# sd_logger.net
KiCad netlist of a schematic drawn in EAGLE
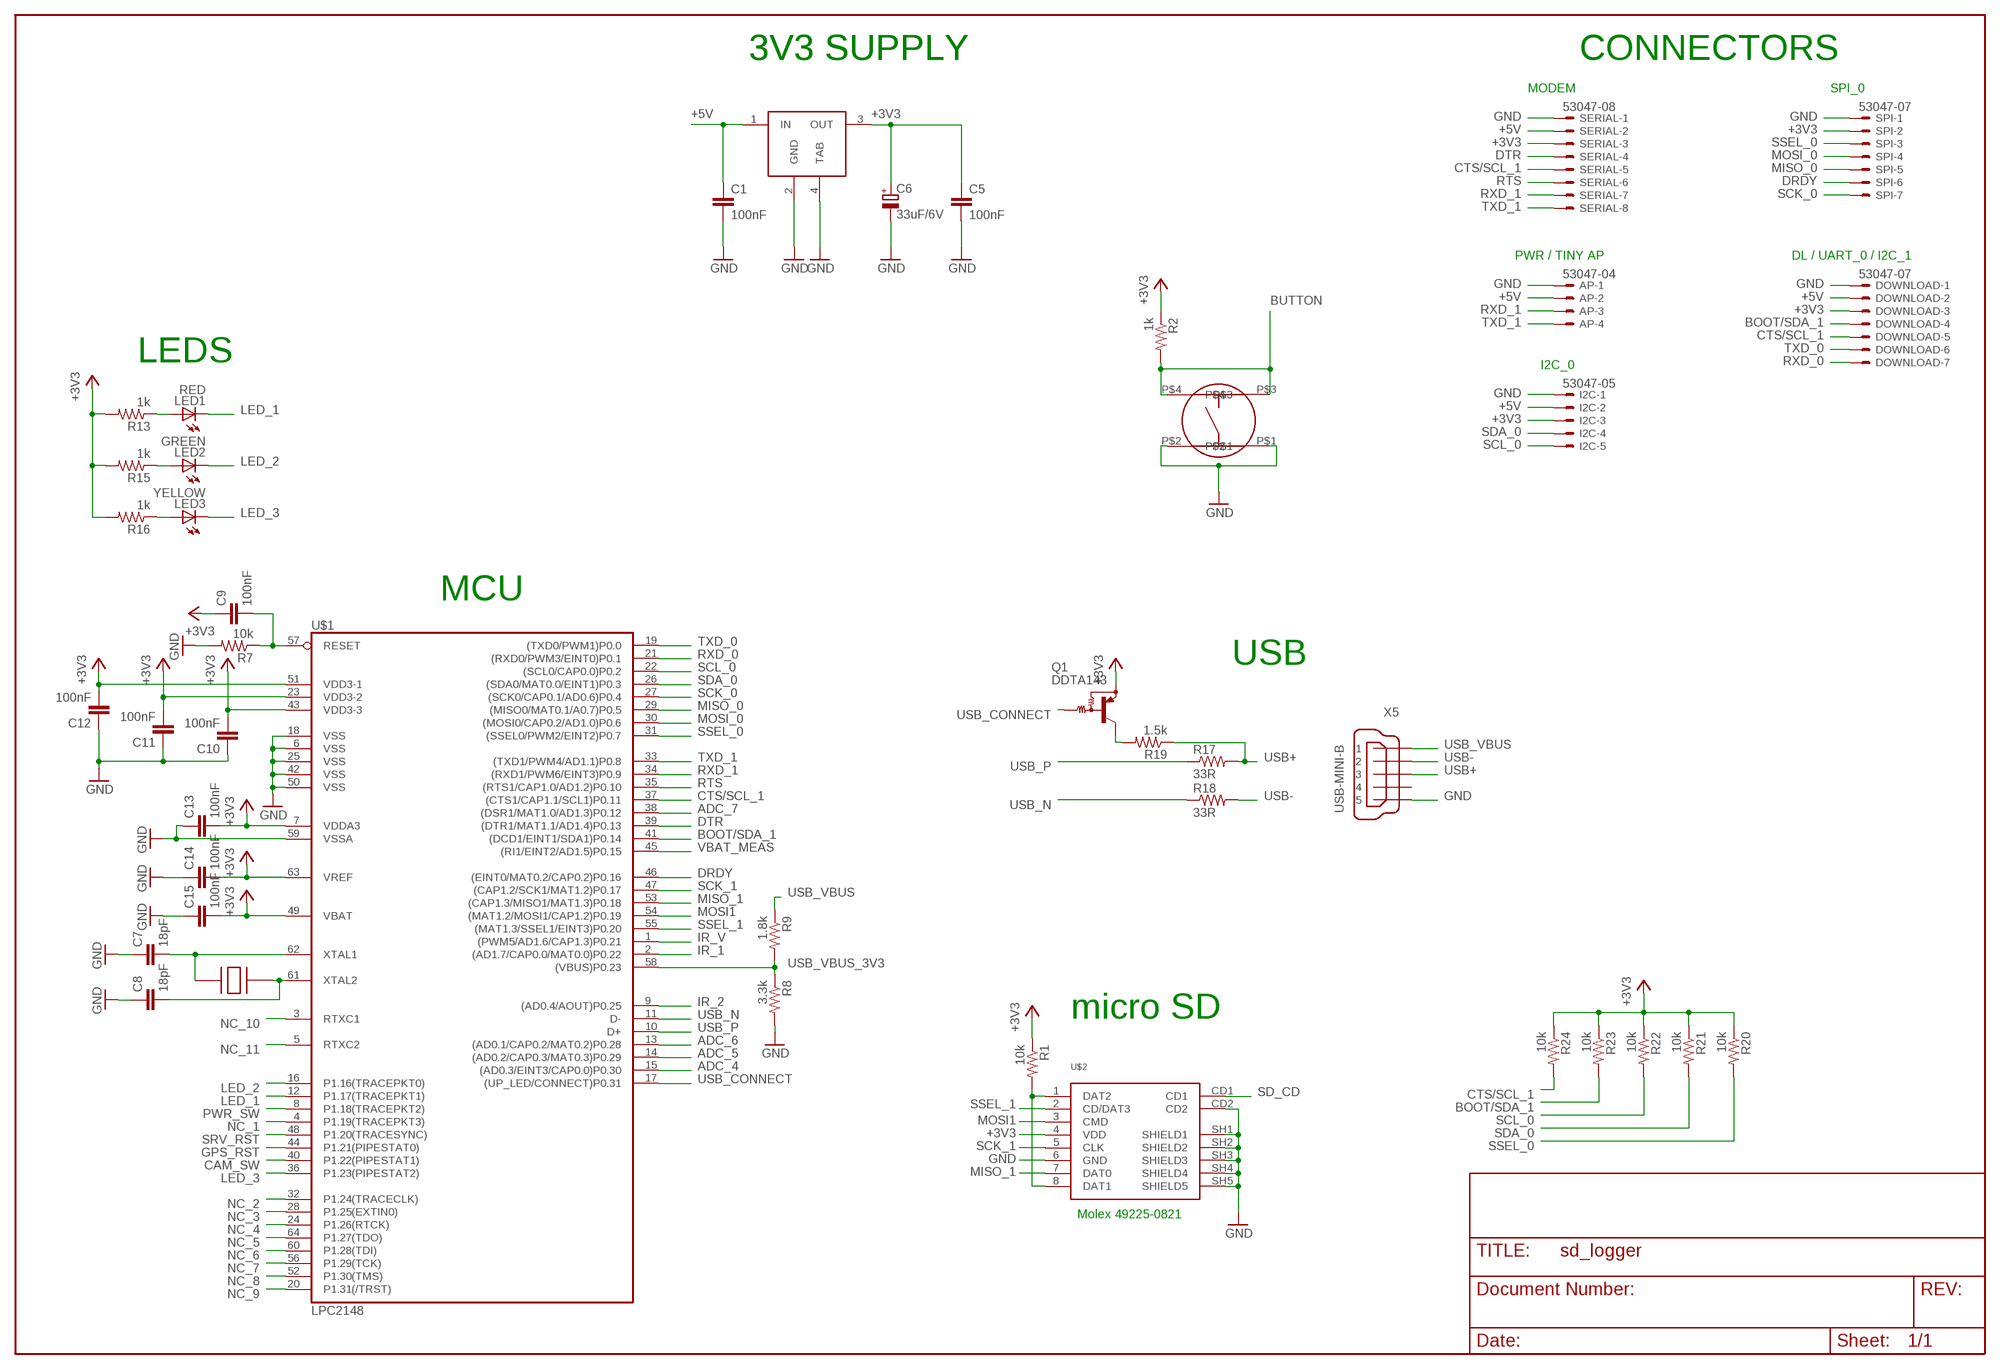
[diagram p0: schematic, sheet 1]

(export (version "E")
  (design (tool "Eeschema 10.0.6"))
  (components
    (comp (ref "AP")
      (value "53047-04")
      (footprint "eagle-import:53047-04")
      (libsource (lib "eagle-import") (part "53?-04047"))
    )
    (comp (ref "C1")
      (value "100nF")
      (footprint "eagle-import:C0603")
      (libsource (lib "eagle-import") (part "C-EUC0603"))
    )
    (comp (ref "C5")
      (value "100nF")
      (footprint "eagle-import:C0603")
      (libsource (lib "eagle-import") (part "C-EUC0603"))
    )
    (comp (ref "C6")
      (value "33uF/6V")
      (footprint "eagle-import:CT3216")
      (libsource (lib "eagle-import") (part "CPOL-EUCT3216"))
    )
    (comp (ref "C7")
      (value "18pF")
      (footprint "eagle-import:C0603")
      (libsource (lib "eagle-import") (part "C-EUC0603"))
    )
    (comp (ref "C8")
      (value "18pF")
      (footprint "eagle-import:C0603")
      (libsource (lib "eagle-import") (part "C-EUC0603"))
    )
    (comp (ref "C9")
      (value "100nF")
      (footprint "eagle-import:C0603")
      (libsource (lib "eagle-import") (part "C-EUC0603"))
    )
    (comp (ref "C10")
      (value "100nF")
      (footprint "eagle-import:C0603")
      (libsource (lib "eagle-import") (part "C-EUC0603"))
    )
    (comp (ref "C11")
      (value "100nF")
      (footprint "eagle-import:C0603")
      (libsource (lib "eagle-import") (part "C-EUC0603"))
    )
    (comp (ref "C12")
      (value "100nF")
      (footprint "eagle-import:C0603")
      (libsource (lib "eagle-import") (part "C-EUC0603"))
    )
    (comp (ref "C13")
      (value "100nF")
      (footprint "eagle-import:C0603")
      (libsource (lib "eagle-import") (part "C-EUC0603"))
    )
    (comp (ref "C14")
      (value "100nF")
      (footprint "eagle-import:C0603")
      (libsource (lib "eagle-import") (part "C-EUC0603"))
    )
    (comp (ref "C15")
      (value "100nF")
      (footprint "eagle-import:C0603")
      (libsource (lib "eagle-import") (part "C-EUC0603"))
    )
    (comp (ref "DOWNLOAD")
      (value "53047-07")
      (footprint "eagle-import:53047-07")
      (libsource (lib "eagle-import") (part "53?-07047"))
    )
    (comp (ref "I2C")
      (value "53047-05")
      (footprint "eagle-import:53047-05")
      (libsource (lib "eagle-import") (part "53?-05047"))
    )
    (comp (ref "LED1")
      (value "RED")
      (footprint "eagle-import:CHIP-LED0805")
      (libsource (lib "eagle-import") (part "LEDCHIP-LED0805"))
    )
    (comp (ref "LED2")
      (value "GREEN")
      (footprint "eagle-import:CHIP-LED0805")
      (libsource (lib "eagle-import") (part "LEDCHIP-LED0805"))
    )
    (comp (ref "LED3")
      (value "YELLOW")
      (footprint "eagle-import:CHIP-LED0805")
      (libsource (lib "eagle-import") (part "LEDCHIP-LED0805"))
    )
    (comp (ref "Q1")
      (value "DDTA143")
      (footprint "eagle-import:SC59-BEC")
      (libsource (lib "eagle-import") (part "MUN2111T1"))
    )
    (comp (ref "R1")
      (value "10k")
      (footprint "eagle-import:R0603@1")
      (libsource (lib "eagle-import") (part "R-US_R0603"))
    )
    (comp (ref "R2")
      (value "1k")
      (footprint "eagle-import:R0603@1")
      (libsource (lib "eagle-import") (part "R-US_R0603"))
    )
    (comp (ref "R7")
      (value "10k")
      (footprint "eagle-import:R0603@1")
      (libsource (lib "eagle-import") (part "R-US_R0603"))
    )
    (comp (ref "R8")
      (value "3.3k")
      (footprint "eagle-import:R0603@1")
      (libsource (lib "eagle-import") (part "R-US_R0603"))
    )
    (comp (ref "R9")
      (value "1.8k")
      (footprint "eagle-import:R0603@1")
      (libsource (lib "eagle-import") (part "R-US_R0603"))
    )
    (comp (ref "R13")
      (value "1k")
      (footprint "eagle-import:R0603@1")
      (libsource (lib "eagle-import") (part "R-US_R0603"))
    )
    (comp (ref "R15")
      (value "1k")
      (footprint "eagle-import:R0603@1")
      (libsource (lib "eagle-import") (part "R-US_R0603"))
    )
    (comp (ref "R16")
      (value "1k")
      (footprint "eagle-import:R0603@1")
      (libsource (lib "eagle-import") (part "R-US_R0603"))
    )
    (comp (ref "R17")
      (value "33R")
      (footprint "eagle-import:R0603@1")
      (libsource (lib "eagle-import") (part "R-US_R0603"))
    )
    (comp (ref "R18")
      (value "33R")
      (footprint "eagle-import:R0603@1")
      (libsource (lib "eagle-import") (part "R-US_R0603"))
    )
    (comp (ref "R19")
      (value "1.5k")
      (footprint "eagle-import:R0603@1")
      (libsource (lib "eagle-import") (part "R-US_R0603"))
    )
    (comp (ref "R20")
      (value "10k")
      (footprint "eagle-import:R0603@1")
      (libsource (lib "eagle-import") (part "R-US_R0603"))
    )
    (comp (ref "R21")
      (value "10k")
      (footprint "eagle-import:R0603@1")
      (libsource (lib "eagle-import") (part "R-US_R0603"))
    )
    (comp (ref "R22")
      (value "10k")
      (footprint "eagle-import:R0603@1")
      (libsource (lib "eagle-import") (part "R-US_R0603"))
    )
    (comp (ref "R23")
      (value "10k")
      (footprint "eagle-import:R0603@1")
      (libsource (lib "eagle-import") (part "R-US_R0603"))
    )
    (comp (ref "R24")
      (value "10k")
      (footprint "eagle-import:R0603@1")
      (libsource (lib "eagle-import") (part "R-US_R0603"))
    )
    (comp (ref "SERIAL")
      (value "53047-08")
      (footprint "eagle-import:53047-08")
      (libsource (lib "eagle-import") (part "53?-08047"))
    )
    (comp (ref "SPI")
      (value "53047-07")
      (footprint "eagle-import:53047-07")
      (libsource (lib "eagle-import") (part "53?-07047"))
    )
    (comp (ref "SW1")
      (value "B3S")
      (footprint "eagle-import:B3S")
      (libsource (lib "eagle-import") (part "B3S"))
    )
    (comp (ref "U$1")
      (value "LPC2148")
      (footprint "eagle-import:SQFP-S-10X10-64")
      (libsource (lib "eagle-import") (part "LPC2148"))
    )
    (comp (ref "U$2")
      (value "MICRO_SD")
      (footprint "eagle-import:SD-MOLEX-49225")
      (libsource (lib "eagle-import") (part "MICRO_SD"))
    )
    (comp (ref "U$3")
      (value "LM3940IMP-3.3")
      (footprint "eagle-import:SOT223-R")
      (libsource (lib "eagle-import") (part "LM3940IMP-3.3"))
    )
    (comp (ref "U$4")
      (value "CRYSTAL_CTS")
      (footprint "eagle-import:CTS_CRYSTAL")
      (libsource (lib "eagle-import") (part "CRYSTAL_CTS"))
    )
    (comp (ref "X5")
      (value "USB-MINI-B")
      (footprint "eagle-import:UX60-MB-5ST")
      (libsource (lib "eagle-import") (part "MINI-USB-UX60-MB-5ST"))
    )
  )
  (nets
    (net (code "1") (name "+3V3") (class "Default")
      (node (ref "C10") (pin "2") (pinfunction "2_2") (pintype "passive"))
      (node (ref "C11") (pin "2") (pinfunction "2_2") (pintype "passive"))
      (node (ref "C12") (pin "2") (pinfunction "2_2") (pintype "passive"))
      (node (ref "C13") (pin "2") (pinfunction "2_2") (pintype "passive"))
      (node (ref "C14") (pin "2") (pinfunction "2_2") (pintype "passive"))
      (node (ref "C15") (pin "2") (pinfunction "2_2") (pintype "passive"))
      (node (ref "C5") (pin "1") (pinfunction "1_1") (pintype "passive"))
      (node (ref "C6") (pin "+") (pinfunction "+_+") (pintype "passive"))
      (node (ref "C9") (pin "1") (pinfunction "1_1") (pintype "passive"))
      (node (ref "DOWNLOAD") (pin "3") (pinfunction "S_3") (pintype "passive"))
      (node (ref "I2C") (pin "3") (pinfunction "S_3") (pintype "passive"))
      (node (ref "Q1") (pin "E") (pinfunction "E_E") (pintype "passive"))
      (node (ref "R1") (pin "1") (pinfunction "1_1") (pintype "passive"))
      (node (ref "R13") (pin "2") (pinfunction "2_2") (pintype "passive"))
      (node (ref "R15") (pin "2") (pinfunction "2_2") (pintype "passive"))
      (node (ref "R16") (pin "2") (pinfunction "2_2") (pintype "passive"))
      (node (ref "R2") (pin "1") (pinfunction "1_1") (pintype "passive"))
      (node (ref "R20") (pin "1") (pinfunction "1_1") (pintype "passive"))
      (node (ref "R21") (pin "1") (pinfunction "1_1") (pintype "passive"))
      (node (ref "R22") (pin "1") (pinfunction "1_1") (pintype "passive"))
      (node (ref "R23") (pin "1") (pinfunction "1_1") (pintype "passive"))
      (node (ref "R24") (pin "1") (pinfunction "1_1") (pintype "passive"))
      (node (ref "SERIAL") (pin "3") (pinfunction "S_3") (pintype "passive"))
      (node (ref "SPI") (pin "2") (pinfunction "S_2") (pintype "passive"))
      (node (ref "U$1") (pin "23") (pinfunction "VDD3-2_23") (pintype "power_in"))
      (node (ref "U$1") (pin "43") (pinfunction "VDD3-3_43") (pintype "power_in"))
      (node (ref "U$1") (pin "49") (pinfunction "VBAT_49") (pintype "power_in"))
      (node (ref "U$1") (pin "51") (pinfunction "VDD3-1_51") (pintype "power_in"))
      (node (ref "U$1") (pin "63") (pinfunction "VREF_63") (pintype "input"))
      (node (ref "U$1") (pin "7") (pinfunction "VDDA3_7") (pintype "power_in"))
      (node (ref "U$2") (pin "4") (pinfunction "VDD_4") (pintype "power_in"))
      (node (ref "U$3") (pin "3") (pinfunction "OUT_3") (pintype "bidirectional"))
    )
    (net (code "2") (name "/+5V") (class "Default")
      (node (ref "AP") (pin "2") (pinfunction "S_2") (pintype "passive"))
      (node (ref "C1") (pin "1") (pinfunction "1_1") (pintype "passive"))
      (node (ref "DOWNLOAD") (pin "2") (pinfunction "S_2") (pintype "passive"))
      (node (ref "I2C") (pin "2") (pinfunction "S_2") (pintype "passive"))
      (node (ref "SERIAL") (pin "2") (pinfunction "S_2") (pintype "passive"))
      (node (ref "U$3") (pin "1") (pinfunction "IN_1") (pintype "bidirectional"))
    )
    (net (code "3") (name "/ADC_4") (class "Default")
      (node (ref "U$1") (pin "15") (pinfunction "(AD0.3/EINT3/CAP0.0)P0.30_15") (pintype "bidirectional"))
    )
    (net (code "4") (name "/ADC_5") (class "Default")
      (node (ref "U$1") (pin "14") (pinfunction "(AD0.2/CAP0.3/MAT0.3)P0.29_14") (pintype "bidirectional"))
    )
    (net (code "5") (name "/ADC_6") (class "Default")
      (node (ref "U$1") (pin "13") (pinfunction "(AD0.1/CAP0.2/MAT0.2)P0.28_13") (pintype "bidirectional"))
    )
    (net (code "6") (name "/ADC_7") (class "Default")
      (node (ref "U$1") (pin "38") (pinfunction "(DSR1/MAT1.0/AD1.3)P0.12_38") (pintype "bidirectional"))
    )
    (net (code "7") (name "/BOOT{slash}SDA_1") (class "Default")
      (node (ref "DOWNLOAD") (pin "4") (pinfunction "S_4") (pintype "passive"))
      (node (ref "R23") (pin "2") (pinfunction "2_2") (pintype "passive"))
      (node (ref "U$1") (pin "41") (pinfunction "(DCD1/EINT1/SDA1)P0.14_41") (pintype "bidirectional"))
    )
    (net (code "8") (name "/BUTTON") (class "Default")
      (node (ref "R2") (pin "2") (pinfunction "2_2") (pintype "passive"))
      (node (ref "SW1") (pin "P$3") (pinfunction "P$3_P$3") (pintype "bidirectional"))
      (node (ref "SW1") (pin "P$4") (pinfunction "P$4_P$4") (pintype "bidirectional"))
    )
    (net (code "9") (name "/CAM_SW") (class "Default")
      (node (ref "U$1") (pin "40") (pinfunction "P1.22(PIPESTAT1)_40") (pintype "bidirectional"))
    )
    (net (code "10") (name "/CTS{slash}SCL_1") (class "Default")
      (node (ref "DOWNLOAD") (pin "5") (pinfunction "S_5") (pintype "passive"))
      (node (ref "R24") (pin "2") (pinfunction "2_2") (pintype "passive"))
      (node (ref "SERIAL") (pin "5") (pinfunction "S_5") (pintype "passive"))
      (node (ref "U$1") (pin "37") (pinfunction "(CTS1/CAP1.1/SCL1)P0.11_37") (pintype "bidirectional"))
    )
    (net (code "11") (name "/DRDY") (class "Default")
      (node (ref "SPI") (pin "6") (pinfunction "S_6") (pintype "passive"))
      (node (ref "U$1") (pin "46") (pinfunction "(EINT0/MAT0.2/CAP0.2)P0.16_46") (pintype "bidirectional"))
    )
    (net (code "12") (name "/DTR") (class "Default")
      (node (ref "SERIAL") (pin "4") (pinfunction "S_4") (pintype "passive"))
      (node (ref "U$1") (pin "39") (pinfunction "(DTR1/MAT1.1/AD1.4)P0.13_39") (pintype "bidirectional"))
    )
    (net (code "13") (name "/GPS_RST") (class "Default")
      (node (ref "U$1") (pin "44") (pinfunction "P1.21(PIPESTAT0)_44") (pintype "bidirectional"))
    )
    (net (code "14") (name "/IR_1") (class "Default")
      (node (ref "U$1") (pin "2") (pinfunction "(AD1.7/CAP0.0/MAT0.0)P0.22_2") (pintype "bidirectional"))
    )
    (net (code "15") (name "/IR_2") (class "Default")
      (node (ref "U$1") (pin "9") (pinfunction "(AD0.4/AOUT)P0.25_9") (pintype "bidirectional"))
    )
    (net (code "16") (name "/IR_V") (class "Default")
      (node (ref "U$1") (pin "1") (pinfunction "(PWM5/AD1.6/CAP1.3)P0.21_1") (pintype "bidirectional"))
    )
    (net (code "17") (name "/LED_1") (class "Default")
      (node (ref "LED1") (pin "C") (pinfunction "C_C") (pintype "passive"))
      (node (ref "U$1") (pin "12") (pinfunction "P1.17(TRACEPKT1)_12") (pintype "bidirectional"))
    )
    (net (code "18") (name "/LED_2") (class "Default")
      (node (ref "LED2") (pin "C") (pinfunction "C_C") (pintype "passive"))
      (node (ref "U$1") (pin "16") (pinfunction "P1.16(TRACEPKT0)_16") (pintype "bidirectional"))
    )
    (net (code "19") (name "/LED_3") (class "Default")
      (node (ref "LED3") (pin "C") (pinfunction "C_C") (pintype "passive"))
      (node (ref "U$1") (pin "36") (pinfunction "P1.23(PIPESTAT2)_36") (pintype "bidirectional"))
    )
    (net (code "20") (name "/MISO_0") (class "Default")
      (node (ref "SPI") (pin "5") (pinfunction "S_5") (pintype "passive"))
      (node (ref "U$1") (pin "29") (pinfunction "(MISO0/MAT0.1/A0.7)P0.5_29") (pintype "bidirectional"))
    )
    (net (code "21") (name "/MISO_1") (class "Default")
      (node (ref "U$1") (pin "53") (pinfunction "(CAP1.3/MISO1/MAT1.3)P0.18_53") (pintype "bidirectional"))
      (node (ref "U$2") (pin "7") (pinfunction "DAT0_7") (pintype "bidirectional"))
    )
    (net (code "22") (name "/MOSI1") (class "Default")
      (node (ref "U$1") (pin "54") (pinfunction "(MAT1.2/MOSI1/CAP1.2)P0.19_54") (pintype "bidirectional"))
      (node (ref "U$2") (pin "3") (pinfunction "CMD_3") (pintype "bidirectional"))
    )
    (net (code "23") (name "/MOSI_0") (class "Default")
      (node (ref "SPI") (pin "4") (pinfunction "S_4") (pintype "passive"))
      (node (ref "U$1") (pin "30") (pinfunction "(MOSI0/CAP0.2/AD1.0)P0.6_30") (pintype "bidirectional"))
    )
    (net (code "24") (name "/NC_1") (class "Default")
      (node (ref "U$1") (pin "4") (pinfunction "P1.19(TRACEPKT3)_4") (pintype "bidirectional"))
    )
    (net (code "25") (name "/NC_2") (class "Default")
      (node (ref "U$1") (pin "32") (pinfunction "P1.24(TRACECLK)_32") (pintype "bidirectional"))
    )
    (net (code "26") (name "/NC_3") (class "Default")
      (node (ref "U$1") (pin "28") (pinfunction "P1.25(EXTIN0)_28") (pintype "bidirectional"))
    )
    (net (code "27") (name "/NC_4") (class "Default")
      (node (ref "U$1") (pin "24") (pinfunction "P1.26(RTCK)_24") (pintype "bidirectional"))
    )
    (net (code "28") (name "/NC_5") (class "Default")
      (node (ref "U$1") (pin "64") (pinfunction "P1.27(TDO)_64") (pintype "bidirectional"))
    )
    (net (code "29") (name "/NC_6") (class "Default")
      (node (ref "U$1") (pin "60") (pinfunction "P1.28(TDI)_60") (pintype "bidirectional"))
    )
    (net (code "30") (name "/NC_7") (class "Default")
      (node (ref "U$1") (pin "56") (pinfunction "P1.29(TCK)_56") (pintype "bidirectional"))
    )
    (net (code "31") (name "/NC_8") (class "Default")
      (node (ref "U$1") (pin "52") (pinfunction "P1.30(TMS)_52") (pintype "bidirectional"))
    )
    (net (code "32") (name "/NC_9") (class "Default")
      (node (ref "U$1") (pin "20") (pinfunction "P1.31(/TRST)_20") (pintype "bidirectional"))
    )
    (net (code "33") (name "/NC_10") (class "Default")
      (node (ref "U$1") (pin "3") (pinfunction "RTXC1_3") (pintype "input"))
    )
    (net (code "34") (name "/NC_11") (class "Default")
      (node (ref "U$1") (pin "5") (pinfunction "RTXC2_5") (pintype "output"))
    )
    (net (code "35") (name "/PWR_SW") (class "Default")
      (node (ref "U$1") (pin "8") (pinfunction "P1.18(TRACEPKT2)_8") (pintype "bidirectional"))
    )
    (net (code "36") (name "/RTS") (class "Default")
      (node (ref "SERIAL") (pin "6") (pinfunction "S_6") (pintype "passive"))
      (node (ref "U$1") (pin "35") (pinfunction "(RTS1/CAP1.0/AD1.2)P0.10_35") (pintype "bidirectional"))
    )
    (net (code "37") (name "/RXD_0") (class "Default")
      (node (ref "DOWNLOAD") (pin "7") (pinfunction "S_7") (pintype "passive"))
      (node (ref "U$1") (pin "21") (pinfunction "(RXD0/PWM3/EINT0)P0.1_21") (pintype "bidirectional"))
    )
    (net (code "38") (name "/RXD_1") (class "Default")
      (node (ref "AP") (pin "3") (pinfunction "S_3") (pintype "passive"))
      (node (ref "SERIAL") (pin "7") (pinfunction "S_7") (pintype "passive"))
      (node (ref "U$1") (pin "34") (pinfunction "(RXD1/PWM6/EINT3)P0.9_34") (pintype "bidirectional"))
    )
    (net (code "39") (name "/SCK_0") (class "Default")
      (node (ref "SPI") (pin "7") (pinfunction "S_7") (pintype "passive"))
      (node (ref "U$1") (pin "27") (pinfunction "(SCK0/CAP0.1/AD0.6)P0.4_27") (pintype "bidirectional"))
    )
    (net (code "40") (name "/SCK_1") (class "Default")
      (node (ref "U$1") (pin "47") (pinfunction "(CAP1.2/SCK1/MAT1.2)P0.17_47") (pintype "bidirectional"))
      (node (ref "U$2") (pin "5") (pinfunction "CLK_5") (pintype "bidirectional"))
    )
    (net (code "41") (name "/SCL_0") (class "Default")
      (node (ref "I2C") (pin "5") (pinfunction "S_5") (pintype "passive"))
      (node (ref "R22") (pin "2") (pinfunction "2_2") (pintype "passive"))
      (node (ref "U$1") (pin "22") (pinfunction "(SCL0/CAP0.0)P0.2_22") (pintype "bidirectional"))
    )
    (net (code "42") (name "/SDA_0") (class "Default")
      (node (ref "I2C") (pin "4") (pinfunction "S_4") (pintype "passive"))
      (node (ref "R21") (pin "2") (pinfunction "2_2") (pintype "passive"))
      (node (ref "U$1") (pin "26") (pinfunction "(SDA0/MAT0.0/EINT1)P0.3_26") (pintype "bidirectional"))
    )
    (net (code "43") (name "/SD_CD") (class "Default")
      (node (ref "U$2") (pin "CD1") (pinfunction "CD1_CD1") (pintype "output"))
    )
    (net (code "44") (name "/SRV_RST") (class "Default")
      (node (ref "U$1") (pin "48") (pinfunction "P1.20(TRACESYNC)_48") (pintype "bidirectional"))
    )
    (net (code "45") (name "/SSEL_0") (class "Default")
      (node (ref "R20") (pin "2") (pinfunction "2_2") (pintype "passive"))
      (node (ref "SPI") (pin "3") (pinfunction "S_3") (pintype "passive"))
      (node (ref "U$1") (pin "31") (pinfunction "(SSEL0/PWM2/EINT2)P0.7_31") (pintype "bidirectional"))
    )
    (net (code "46") (name "/SSEL_1") (class "Default")
      (node (ref "U$1") (pin "55") (pinfunction "(MAT1.3/SSEL1/EINT3)P0.20_55") (pintype "bidirectional"))
      (node (ref "U$2") (pin "2") (pinfunction "CD/DAT3_2") (pintype "bidirectional"))
    )
    (net (code "47") (name "/TXD_0") (class "Default")
      (node (ref "DOWNLOAD") (pin "6") (pinfunction "S_6") (pintype "passive"))
      (node (ref "U$1") (pin "19") (pinfunction "(TXD0/PWM1)P0.0_19") (pintype "bidirectional"))
    )
    (net (code "48") (name "/TXD_1") (class "Default")
      (node (ref "AP") (pin "4") (pinfunction "S_4") (pintype "passive"))
      (node (ref "SERIAL") (pin "8") (pinfunction "S_8") (pintype "passive"))
      (node (ref "U$1") (pin "33") (pinfunction "(TXD1/PWM4/AD1.1)P0.8_33") (pintype "bidirectional"))
    )
    (net (code "49") (name "/USB+") (class "Default")
      (node (ref "R17") (pin "2") (pinfunction "2_2") (pintype "passive"))
      (node (ref "R19") (pin "1") (pinfunction "1_1") (pintype "passive"))
      (node (ref "X5") (pin "3") (pinfunction "3_3") (pintype "input"))
    )
    (net (code "50") (name "/USB-") (class "Default")
      (node (ref "R18") (pin "2") (pinfunction "2_2") (pintype "passive"))
      (node (ref "X5") (pin "2") (pinfunction "2_2") (pintype "input"))
    )
    (net (code "51") (name "/USB_CONNECT") (class "Default")
      (node (ref "Q1") (pin "B") (pinfunction "B_B") (pintype "passive"))
      (node (ref "U$1") (pin "17") (pinfunction "(UP_LED/CONNECT)P0.31_17") (pintype "output"))
    )
    (net (code "52") (name "/USB_N") (class "Default")
      (node (ref "R18") (pin "1") (pinfunction "1_1") (pintype "passive"))
      (node (ref "U$1") (pin "11") (pinfunction "D-_11") (pintype "bidirectional"))
    )
    (net (code "53") (name "/USB_P") (class "Default")
      (node (ref "R17") (pin "1") (pinfunction "1_1") (pintype "passive"))
      (node (ref "U$1") (pin "10") (pinfunction "D+_10") (pintype "bidirectional"))
    )
    (net (code "54") (name "/USB_VBUS") (class "Default")
      (node (ref "R9") (pin "1") (pinfunction "1_1") (pintype "passive"))
      (node (ref "X5") (pin "1") (pinfunction "1_1") (pintype "input"))
    )
    (net (code "55") (name "/USB_VBUS_3V3") (class "Default")
      (node (ref "R8") (pin "1") (pinfunction "1_1") (pintype "passive"))
      (node (ref "R9") (pin "2") (pinfunction "2_2") (pintype "passive"))
      (node (ref "U$1") (pin "58") (pinfunction "(VBUS)P0.23_58") (pintype "bidirectional"))
    )
    (net (code "56") (name "/VBAT_MEAS") (class "Default")
      (node (ref "U$1") (pin "45") (pinfunction "(RI1/EINT2/AD1.5)P0.15_45") (pintype "bidirectional"))
    )
    (net (code "57") (name "GND") (class "Default")
      (node (ref "AP") (pin "1") (pinfunction "S_1") (pintype "passive"))
      (node (ref "C1") (pin "2") (pinfunction "2_2") (pintype "passive"))
      (node (ref "C10") (pin "1") (pinfunction "1_1") (pintype "passive"))
      (node (ref "C11") (pin "1") (pinfunction "1_1") (pintype "passive"))
      (node (ref "C12") (pin "1") (pinfunction "1_1") (pintype "passive"))
      (node (ref "C13") (pin "1") (pinfunction "1_1") (pintype "passive"))
      (node (ref "C14") (pin "1") (pinfunction "1_1") (pintype "passive"))
      (node (ref "C15") (pin "1") (pinfunction "1_1") (pintype "passive"))
      (node (ref "C5") (pin "2") (pinfunction "2_2") (pintype "passive"))
      (node (ref "C6") (pin "-") (pinfunction "-_-") (pintype "passive"))
      (node (ref "C7") (pin "1") (pinfunction "1_1") (pintype "passive"))
      (node (ref "C8") (pin "1") (pinfunction "1_1") (pintype "passive"))
      (node (ref "DOWNLOAD") (pin "1") (pinfunction "S_1") (pintype "passive"))
      (node (ref "I2C") (pin "1") (pinfunction "S_1") (pintype "passive"))
      (node (ref "R7") (pin "2") (pinfunction "2_2") (pintype "passive"))
      (node (ref "R8") (pin "2") (pinfunction "2_2") (pintype "passive"))
      (node (ref "SERIAL") (pin "1") (pinfunction "S_1") (pintype "passive"))
      (node (ref "SPI") (pin "1") (pinfunction "S_1") (pintype "passive"))
      (node (ref "SW1") (pin "P$1") (pinfunction "P$1_P$1") (pintype "bidirectional"))
      (node (ref "SW1") (pin "P$2") (pinfunction "P$2_P$2") (pintype "bidirectional"))
      (node (ref "U$1") (pin "18") (pinfunction "VSS_18") (pintype "power_in"))
      (node (ref "U$1") (pin "25") (pinfunction "VSS_25") (pintype "power_in"))
      (node (ref "U$1") (pin "42") (pinfunction "VSS_42") (pintype "power_in"))
      (node (ref "U$1") (pin "50") (pinfunction "VSS_50") (pintype "power_in"))
      (node (ref "U$1") (pin "59") (pinfunction "VSSA_59") (pintype "power_in"))
      (node (ref "U$1") (pin "6") (pinfunction "VSS_6") (pintype "power_in"))
      (node (ref "U$2") (pin "6") (pinfunction "GND_6") (pintype "power_in"))
      (node (ref "U$2") (pin "CD2") (pinfunction "CD2_CD2") (pintype "output"))
      (node (ref "U$2") (pin "SH1") (pinfunction "SHIELD1_SH1") (pintype "power_in"))
      (node (ref "U$2") (pin "SH2") (pinfunction "SHIELD2_SH2") (pintype "power_in"))
      (node (ref "U$2") (pin "SH3") (pinfunction "SHIELD3_SH3") (pintype "power_in"))
      (node (ref "U$2") (pin "SH4") (pinfunction "SHIELD4_SH4") (pintype "power_in"))
      (node (ref "U$2") (pin "SH5") (pinfunction "SHIELD5_SH5") (pintype "power_in"))
      (node (ref "U$3") (pin "2") (pinfunction "GND_2") (pintype "bidirectional"))
      (node (ref "U$3") (pin "4") (pinfunction "TAB_4") (pintype "bidirectional"))
      (node (ref "X5") (pin "5") (pinfunction "5_5") (pintype "input"))
    )
    (net (code "58") (name "Net-(LED1-PadA)") (class "Default")
      (node (ref "LED1") (pin "A") (pinfunction "A_A") (pintype "passive"))
      (node (ref "R13") (pin "1") (pinfunction "1_1") (pintype "passive"))
    )
    (net (code "59") (name "Net-(LED2-PadA)") (class "Default")
      (node (ref "LED2") (pin "A") (pinfunction "A_A") (pintype "passive"))
      (node (ref "R15") (pin "1") (pinfunction "1_1") (pintype "passive"))
    )
    (net (code "60") (name "Net-(LED3-PadA)") (class "Default")
      (node (ref "LED3") (pin "A") (pinfunction "A_A") (pintype "passive"))
      (node (ref "R16") (pin "1") (pinfunction "1_1") (pintype "passive"))
    )
    (net (code "61") (name "Net-(Q1-PadC)") (class "Default")
      (node (ref "Q1") (pin "C") (pinfunction "C_C") (pintype "passive"))
      (node (ref "R19") (pin "2") (pinfunction "2_2") (pintype "passive"))
    )
    (net (code "62") (name "Net-(U$1-RESET)") (class "Default")
      (node (ref "C9") (pin "2") (pinfunction "2_2") (pintype "passive"))
      (node (ref "R7") (pin "1") (pinfunction "1_1") (pintype "passive"))
      (node (ref "U$1") (pin "57") (pinfunction "RESET_57") (pintype "input"))
    )
    (net (code "63") (name "Net-(U$1-XTAL1)") (class "Default")
      (node (ref "C7") (pin "2") (pinfunction "2_2") (pintype "passive"))
      (node (ref "U$1") (pin "62") (pinfunction "XTAL1_62") (pintype "input"))
      (node (ref "U$4") (pin "P$1") (pinfunction "P$1_P$1") (pintype "bidirectional"))
    )
    (net (code "64") (name "Net-(U$1-XTAL2)") (class "Default")
      (node (ref "C8") (pin "2") (pinfunction "2_2") (pintype "passive"))
      (node (ref "U$1") (pin "61") (pinfunction "XTAL2_61") (pintype "output"))
      (node (ref "U$4") (pin "P$3") (pinfunction "P$2_P$3") (pintype "bidirectional"))
    )
    (net (code "65") (name "Net-(U$2-DAT1)") (class "Default")
      (node (ref "R1") (pin "2") (pinfunction "2_2") (pintype "passive"))
      (node (ref "U$2") (pin "1") (pinfunction "DAT2_1") (pintype "bidirectional"))
      (node (ref "U$2") (pin "8") (pinfunction "DAT1_8") (pintype "bidirectional"))
    )
    (net (code "66") (name "unconnected-(X5-Pad4)") (class "Default")
      (node (ref "X5") (pin "4") (pinfunction "4_4") (pintype "input"))
    )
  )
)
